# ESP-3D.net
KiCad netlist of a schematic drawn in Altium Designer
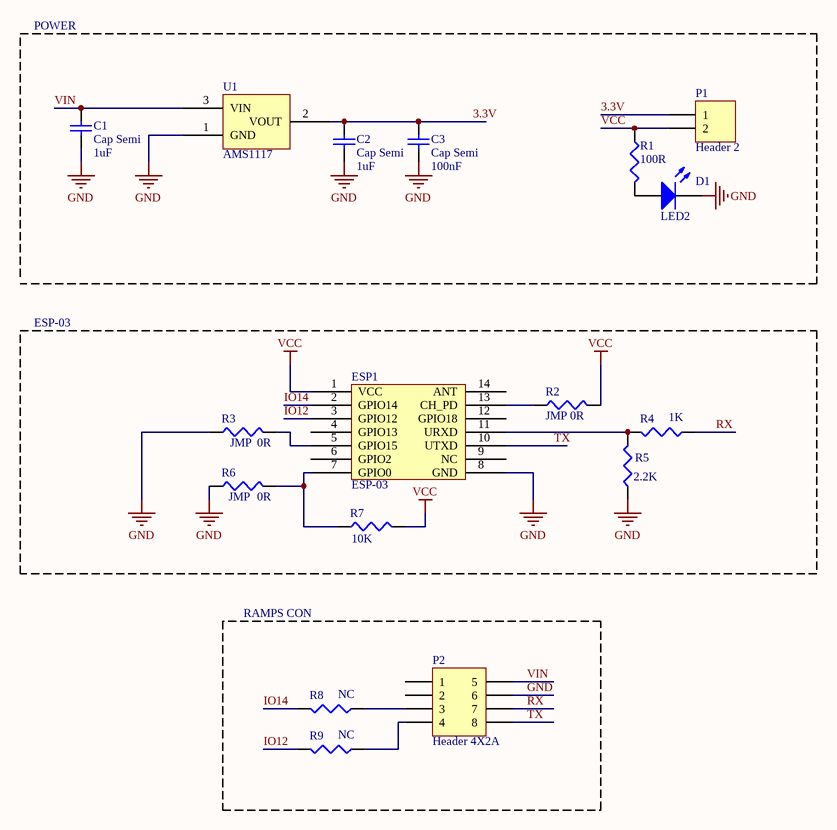
[diagram p0: ESP-3D.SchDoc]

(export (version "E")
  (design (tool "Eeschema 10.0.6"))
  (components
    (comp (ref "C1")
      (value "Cap Semi")
      (footprint "1608[0603]")
      (description "Capacitor (Semiconductor SIM Model)")
      (fields (field (name "ALTIUM_VALUE") "1uF") (field (name "PUBLISHER") "Altium Limited"))
      (libsource (lib "Miscellaneous Devices") (part "Cap Semi"))
    )
    (comp (ref "C2")
      (value "Cap Semi")
      (footprint "1608[0603]")
      (description "Capacitor (Semiconductor SIM Model)")
      (fields (field (name "ALTIUM_VALUE") "1uF") (field (name "PUBLISHER") "Altium Limited"))
      (libsource (lib "Miscellaneous Devices") (part "Cap Semi"))
    )
    (comp (ref "C3")
      (value "Cap Semi")
      (footprint "1608[0603]")
      (description "Capacitor (Semiconductor SIM Model)")
      (fields (field (name "ALTIUM_VALUE") "100nF") (field (name "PUBLISHER") "Altium Limited"))
      (libsource (lib "Miscellaneous Devices") (part "Cap Semi"))
    )
    (comp (ref "D1")
      (value "LED2")
      (footprint "Miscellaneous Devices:C0805")
      (description "Typical RED, GREEN, YELLOW, AMBER GaAs LED")
      (fields (field (name "PUBLISHER") "Altium Limited"))
      (libsource (lib "Miscellaneous Devices") (part "LED2"))
    )
    (comp (ref "ESP1")
      (value "ESP-03")
      (footprint "ESP-03")
      (libsource (lib "Library_triggerr") (part "ESP-03"))
    )
    (comp (ref "P1")
      (value "Header 2")
      (footprint "HDR1X2")
      (description "Header, 2-Pin")
      (fields (field (name "PUBLISHER") "Altium Limited"))
      (libsource (lib "Miscellaneous Connectors") (part "Header 2"))
    )
    (comp (ref "P2")
      (value "Header 4X2A")
      (footprint "HDR2X4_CEN")
      (description "Header, 4-Pin, Dual row")
      (fields (field (name "PUBLISHER") "Altium Limited"))
      (libsource (lib "Miscellaneous Connectors") (part "Header 4X2A"))
    )
    (comp (ref "R1")
      (value "100R")
      (footprint "J1-0603")
      (description "Resistor")
      (fields (field (name "Comment") "JMP") (field (name "PUBLISHER") "Altium Limited"))
      (libsource (lib "Miscellaneous Devices") (part "Res3"))
    )
    (comp (ref "R2")
      (value "JMP")
      (footprint "J1-0603")
      (description "Resistor")
      (fields (field (name "ALTIUM_VALUE") "0R") (field (name "PUBLISHER") "Altium Limited"))
      (libsource (lib "Miscellaneous Devices") (part "Res3"))
    )
    (comp (ref "R3")
      (value "JMP")
      (footprint "J1-0603")
      (description "Resistor")
      (fields (field (name "ALTIUM_VALUE") "0R") (field (name "PUBLISHER") "Altium Limited"))
      (libsource (lib "Miscellaneous Devices") (part "Res3"))
    )
    (comp (ref "R4")
      (value "1K")
      (footprint "J1-0603")
      (description "Resistor")
      (fields (field (name "Comment") "JMP") (field (name "PUBLISHER") "Altium Limited"))
      (libsource (lib "Miscellaneous Devices") (part "Res3"))
    )
    (comp (ref "R5")
      (value "2.2K")
      (footprint "J1-0603")
      (description "Resistor")
      (fields (field (name "Comment") "JMP") (field (name "PUBLISHER") "Altium Limited"))
      (libsource (lib "Miscellaneous Devices") (part "Res3"))
    )
    (comp (ref "R6")
      (value "JMP")
      (footprint "J1-0603")
      (description "Resistor")
      (fields (field (name "ALTIUM_VALUE") "0R") (field (name "PUBLISHER") "Altium Limited"))
      (libsource (lib "Miscellaneous Devices") (part "Res3"))
    )
    (comp (ref "R7")
      (value "10K")
      (footprint "J1-0603")
      (description "Resistor")
      (fields (field (name "Comment") "P") (field (name "PUBLISHER") "Altium Limited"))
      (libsource (lib "Miscellaneous Devices") (part "Res3"))
    )
    (comp (ref "R8")
      (value "NC")
      (footprint "J1-0603")
      (description "Resistor")
      (fields (field (name "Comment") "JMP") (field (name "PUBLISHER") "Altium Limited"))
      (libsource (lib "Miscellaneous Devices") (part "Res3"))
    )
    (comp (ref "R9")
      (value "NC")
      (footprint "J1-0603")
      (description "Resistor")
      (fields (field (name "Comment") "JMP") (field (name "PUBLISHER") "Altium Limited"))
      (libsource (lib "Miscellaneous Devices") (part "Res3"))
    )
    (comp (ref "U1")
      (value "AMS1117")
      (footprint "SOT223_N")
      (libsource (lib "Library_triggerr") (part "AMS1117"))
    )
  )
  (nets
    (net (code "1") (name "/3.3V") (class "Default")
      (node (ref "C2") (pin "2") (pinfunction "2_2") (pintype "passive"))
      (node (ref "C3") (pin "2") (pinfunction "2_2") (pintype "passive"))
      (node (ref "P1") (pin "1") (pinfunction "1_1") (pintype "passive"))
      (node (ref "U1") (pin "2") (pinfunction "VOUT_2") (pintype "passive"))
    )
    (net (code "2") (name "/IO12") (class "Default")
      (node (ref "ESP1") (pin "3") (pinfunction "GPIO12_3") (pintype "passive"))
      (node (ref "R9") (pin "2") (pinfunction "2_2") (pintype "passive"))
    )
    (net (code "3") (name "/IO14") (class "Default")
      (node (ref "ESP1") (pin "2") (pinfunction "GPIO14_2") (pintype "passive"))
      (node (ref "R8") (pin "2") (pinfunction "2_2") (pintype "passive"))
    )
    (net (code "4") (name "/RX") (class "Default")
      (node (ref "P2") (pin "7") (pinfunction "7_7") (pintype "passive"))
      (node (ref "R4") (pin "1") (pinfunction "1_1") (pintype "passive"))
    )
    (net (code "5") (name "/TX") (class "Default")
      (node (ref "ESP1") (pin "10") (pinfunction "UTXD_10") (pintype "passive"))
      (node (ref "P2") (pin "8") (pinfunction "8_8") (pintype "passive"))
    )
    (net (code "6") (name "/VIN") (class "Default")
      (node (ref "C1") (pin "2") (pinfunction "2_2") (pintype "passive"))
      (node (ref "P2") (pin "5") (pinfunction "5_5") (pintype "passive"))
      (node (ref "U1") (pin "3") (pinfunction "VIN_3") (pintype "passive"))
    )
    (net (code "7") (name "GND") (class "Default")
      (node (ref "C1") (pin "1") (pinfunction "1_1") (pintype "passive"))
      (node (ref "C2") (pin "1") (pinfunction "1_1") (pintype "passive"))
      (node (ref "C3") (pin "1") (pinfunction "1_1") (pintype "passive"))
      (node (ref "D1") (pin "2") (pinfunction "K_2") (pintype "passive"))
      (node (ref "ESP1") (pin "8") (pinfunction "GND_8") (pintype "passive"))
      (node (ref "P2") (pin "6") (pinfunction "6_6") (pintype "passive"))
      (node (ref "R3") (pin "1") (pinfunction "1_1") (pintype "passive"))
      (node (ref "R5") (pin "1") (pinfunction "1_1") (pintype "passive"))
      (node (ref "R6") (pin "1") (pinfunction "1_1") (pintype "passive"))
      (node (ref "U1") (pin "1") (pinfunction "GND_1") (pintype "passive"))
    )
    (net (code "8") (name "Net-(D1-A)") (class "Default")
      (node (ref "D1") (pin "1") (pinfunction "A_1") (pintype "passive"))
      (node (ref "R1") (pin "2") (pinfunction "2_2") (pintype "passive"))
    )
    (net (code "9") (name "Net-(ESP1-CH_PD)") (class "Default")
      (node (ref "ESP1") (pin "13") (pinfunction "CH_PD_13") (pintype "passive"))
      (node (ref "R2") (pin "1") (pinfunction "1_1") (pintype "passive"))
    )
    (net (code "10") (name "Net-(ESP1-GPIO0)") (class "Default")
      (node (ref "ESP1") (pin "7") (pinfunction "GPIO0_7") (pintype "passive"))
      (node (ref "R6") (pin "2") (pinfunction "2_2") (pintype "passive"))
      (node (ref "R7") (pin "1") (pinfunction "1_1") (pintype "passive"))
    )
    (net (code "11") (name "Net-(ESP1-GPIO15)") (class "Default")
      (node (ref "ESP1") (pin "5") (pinfunction "GPIO15_5") (pintype "passive"))
      (node (ref "R3") (pin "2") (pinfunction "2_2") (pintype "passive"))
    )
    (net (code "12") (name "Net-(ESP1-URXD)") (class "Default")
      (node (ref "ESP1") (pin "11") (pinfunction "URXD_11") (pintype "passive"))
      (node (ref "R4") (pin "2") (pinfunction "2_2") (pintype "passive"))
      (node (ref "R5") (pin "2") (pinfunction "2_2") (pintype "passive"))
    )
    (net (code "13") (name "Net-(P2-Pad3)") (class "Default")
      (node (ref "P2") (pin "3") (pinfunction "3_3") (pintype "passive"))
      (node (ref "R8") (pin "1") (pinfunction "1_1") (pintype "passive"))
    )
    (net (code "14") (name "Net-(P2-Pad4)") (class "Default")
      (node (ref "P2") (pin "4") (pinfunction "4_4") (pintype "passive"))
      (node (ref "R9") (pin "1") (pinfunction "1_1") (pintype "passive"))
    )
    (net (code "15") (name "VCC") (class "Default")
      (node (ref "ESP1") (pin "1") (pinfunction "VCC_1") (pintype "passive"))
      (node (ref "P1") (pin "2") (pinfunction "2_2") (pintype "passive"))
      (node (ref "R1") (pin "1") (pinfunction "1_1") (pintype "passive"))
      (node (ref "R2") (pin "2") (pinfunction "2_2") (pintype "passive"))
      (node (ref "R7") (pin "2") (pinfunction "2_2") (pintype "passive"))
    )
    (net (code "16") (name "unconnected-(ESP1-ANT-Pad14)") (class "Default")
      (node (ref "ESP1") (pin "14") (pinfunction "ANT_14") (pintype "passive"))
    )
    (net (code "17") (name "unconnected-(ESP1-GPIO2-Pad6)") (class "Default")
      (node (ref "ESP1") (pin "6") (pinfunction "GPIO2_6") (pintype "passive"))
    )
    (net (code "18") (name "unconnected-(ESP1-GPIO13-Pad4)") (class "Default")
      (node (ref "ESP1") (pin "4") (pinfunction "GPIO13_4") (pintype "passive"))
    )
    (net (code "19") (name "unconnected-(ESP1-GPIO18-Pad12)") (class "Default")
      (node (ref "ESP1") (pin "12") (pinfunction "GPIO18_12") (pintype "passive"))
    )
    (net (code "20") (name "unconnected-(ESP1-NC-Pad9)") (class "Default")
      (node (ref "ESP1") (pin "9") (pinfunction "NC_9") (pintype "passive"))
    )
    (net (code "21") (name "unconnected-(P2-Pad1)") (class "Default")
      (node (ref "P2") (pin "1") (pinfunction "1_1") (pintype "passive"))
    )
    (net (code "22") (name "unconnected-(P2-Pad2)") (class "Default")
      (node (ref "P2") (pin "2") (pinfunction "2_2") (pintype "passive"))
    )
  )
)
